# AeroModule_2021-02-14.net
KiCad netlist of a schematic drawn in EasyEDA
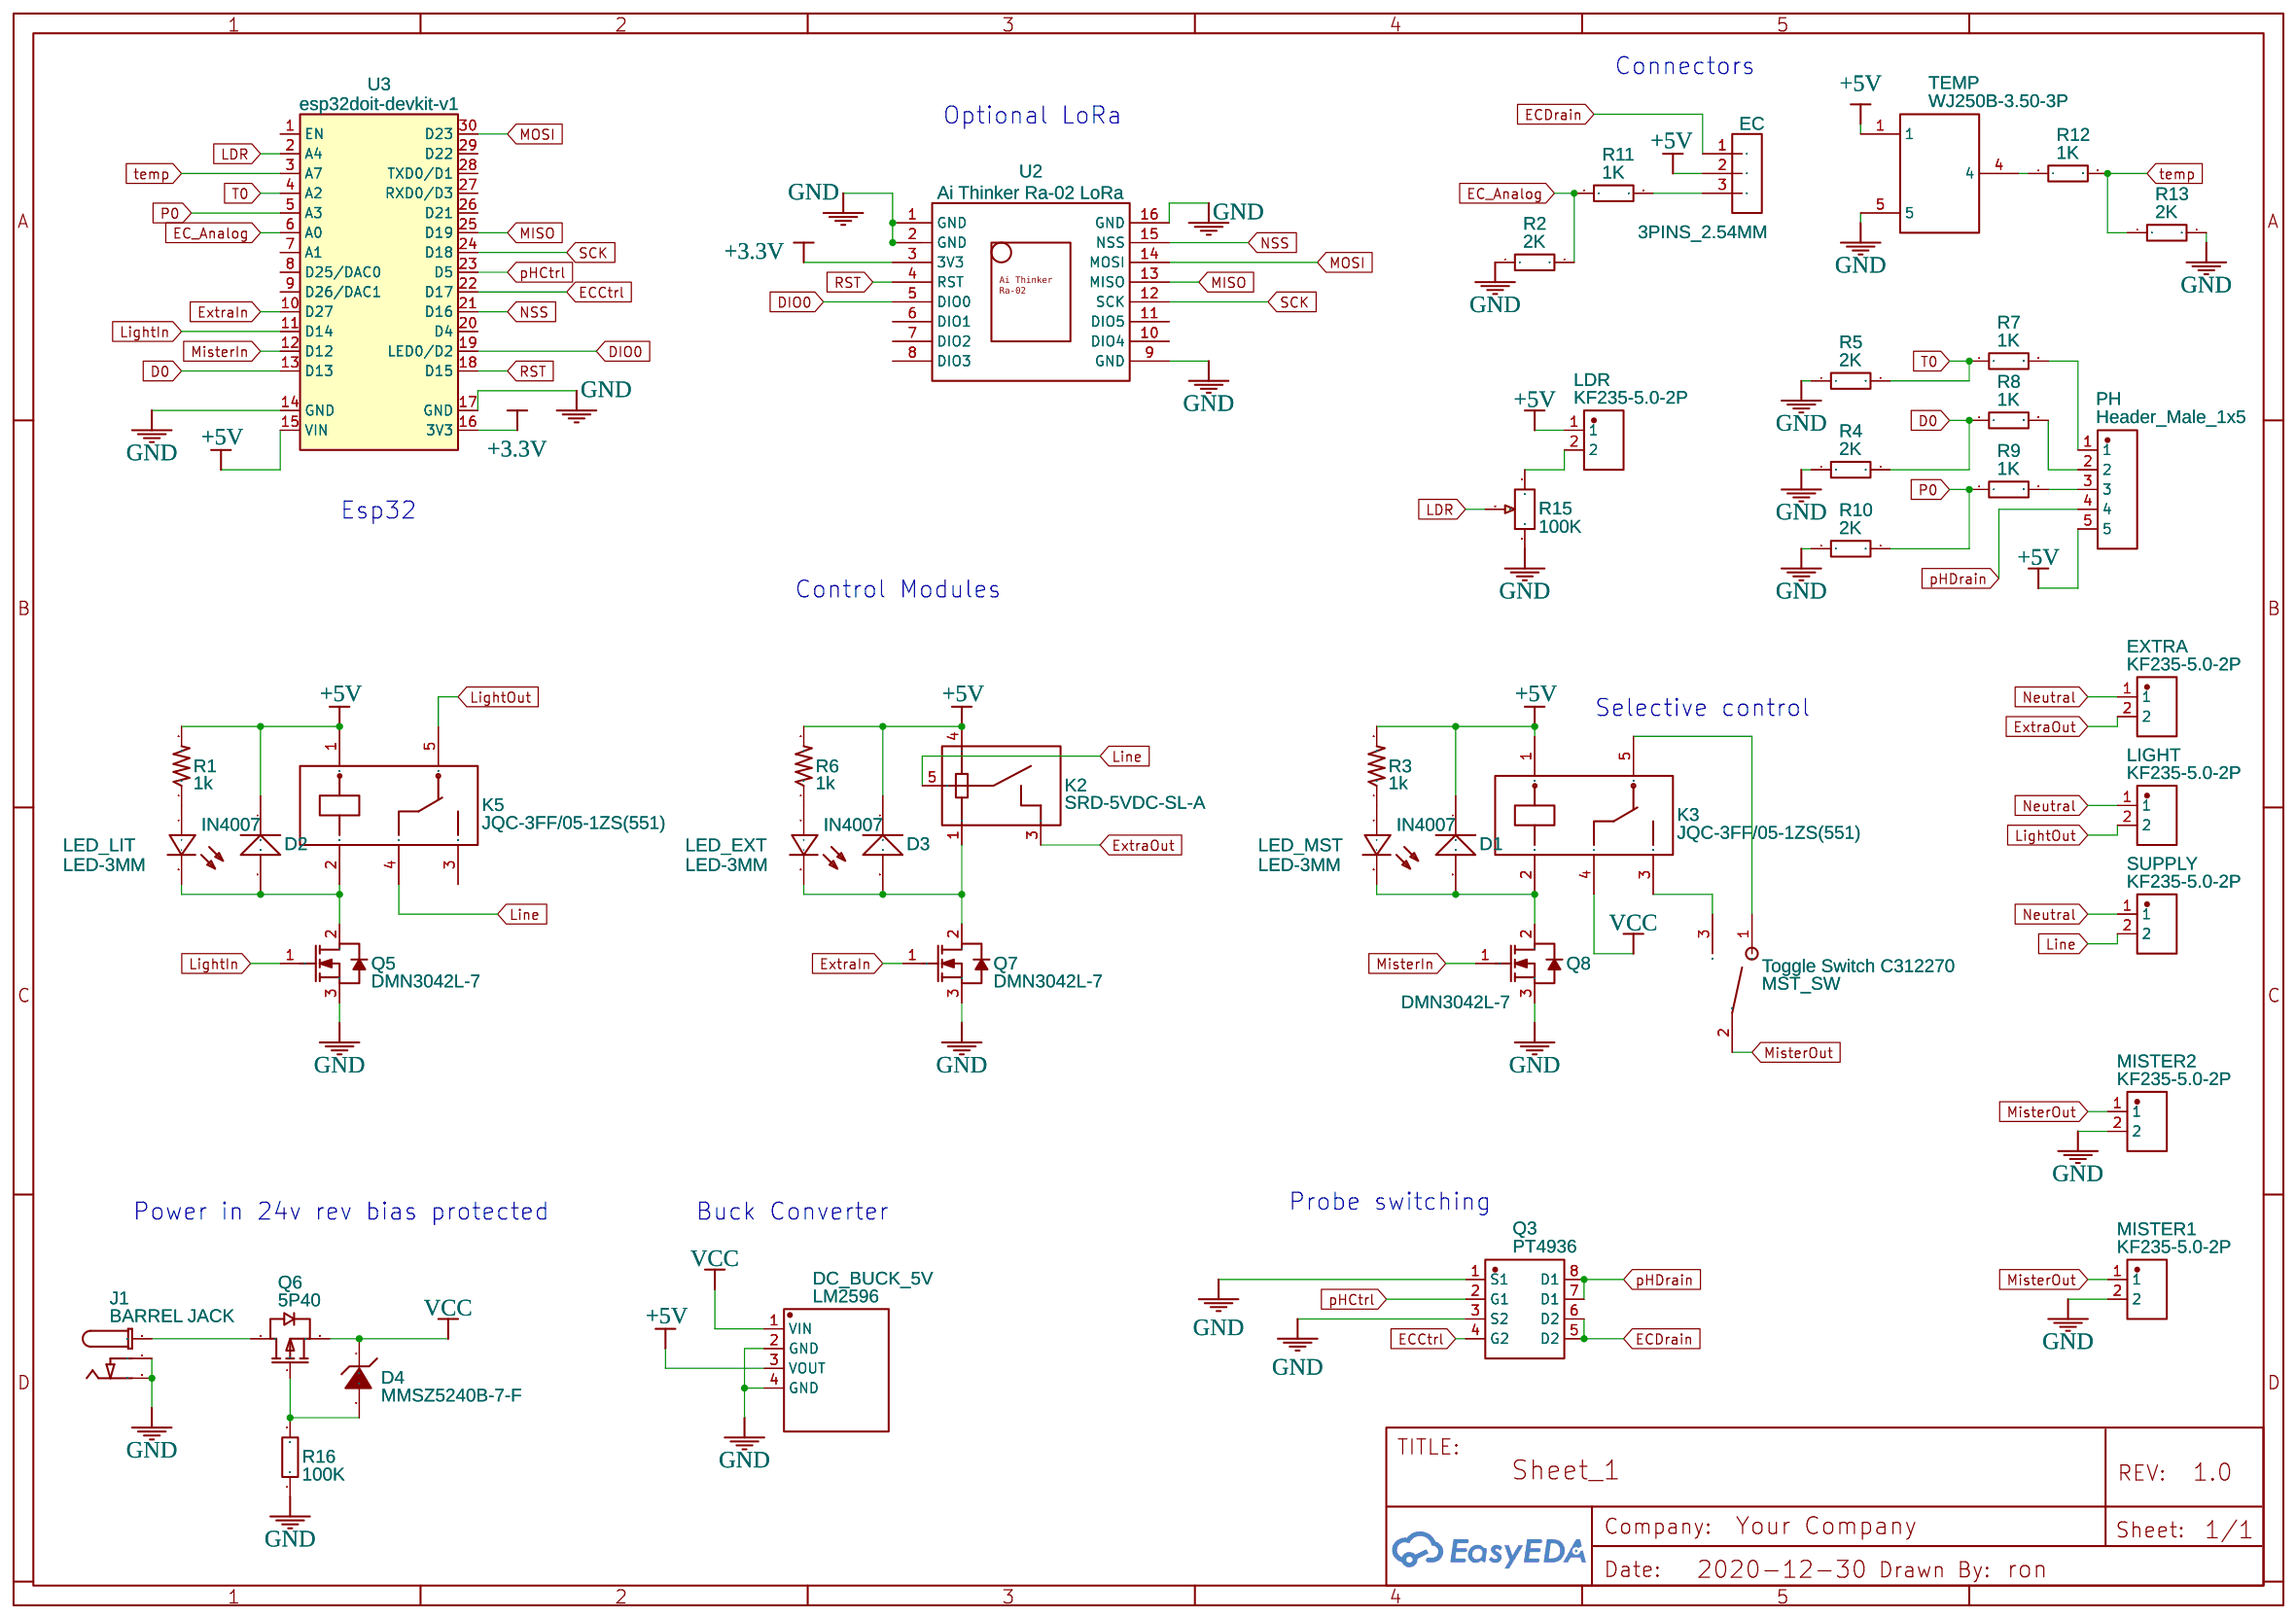
[diagram p0: Sheet_1]
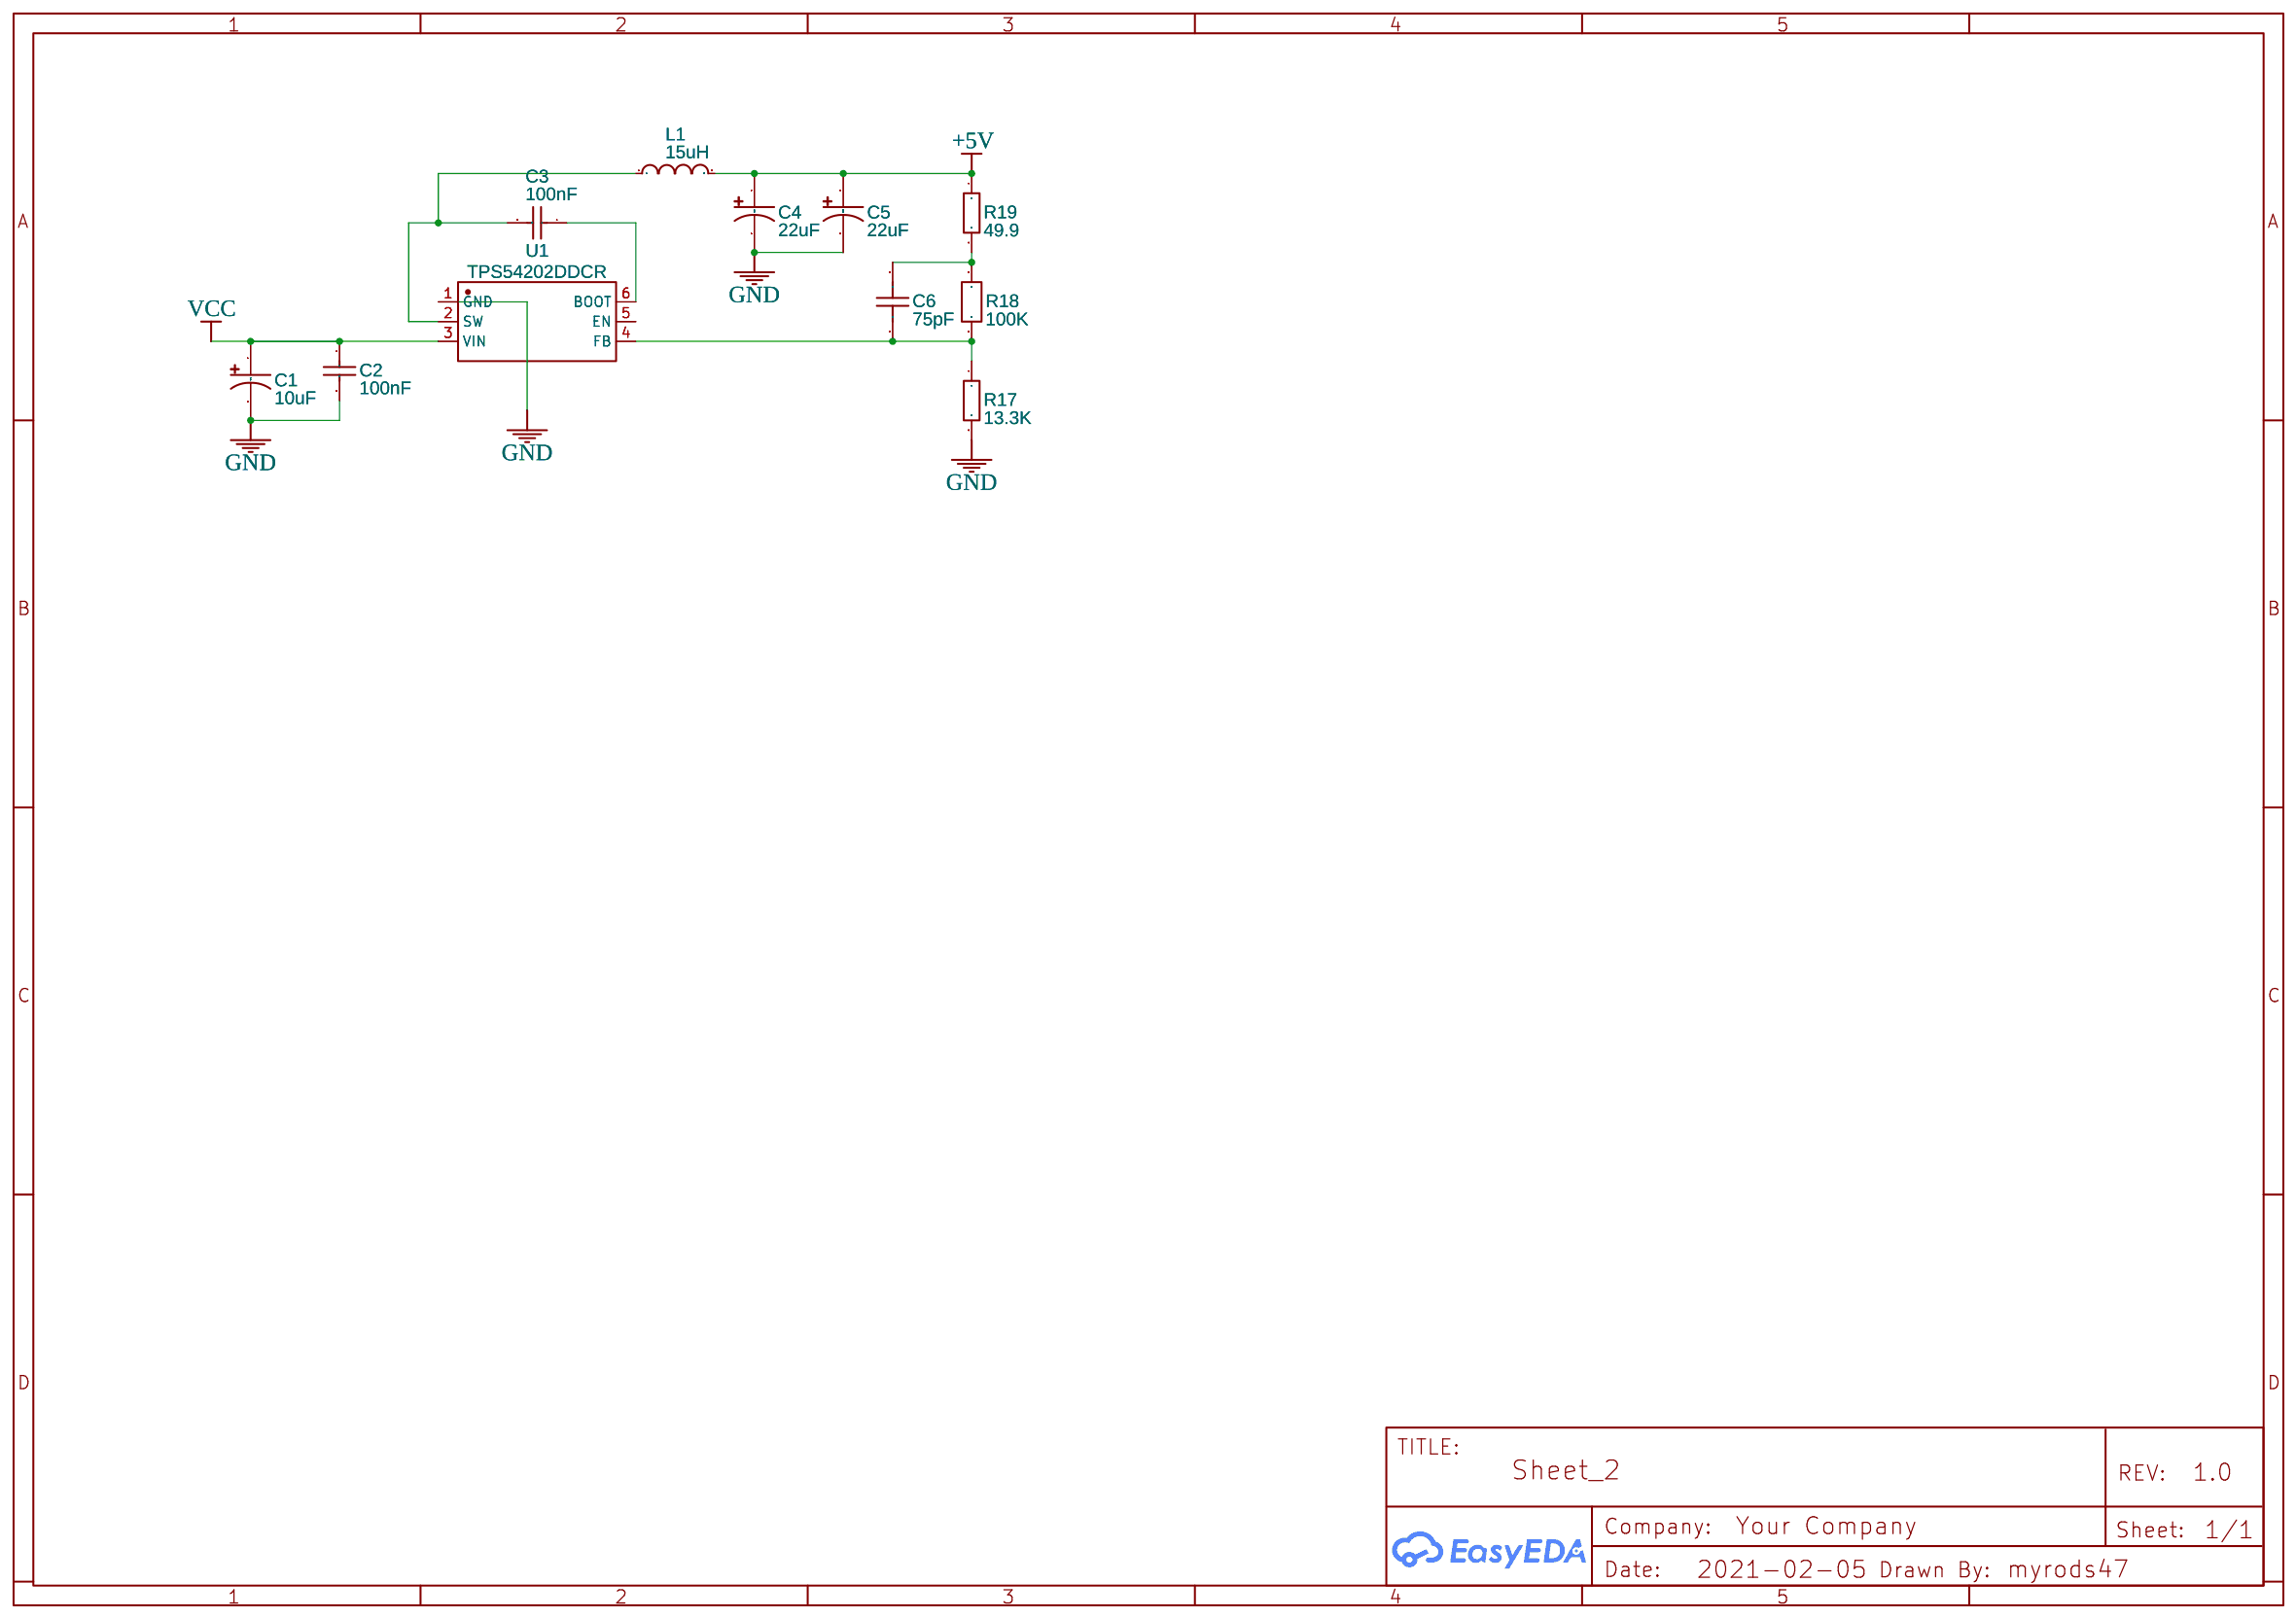
[diagram p1: Power]

(export (version "E")
  (design (tool "Eeschema 10.0.6"))
  (components
    (comp (ref "D1")
      (value "IN4007")
      (fields (field (name "BOM_Manufacturer Part") "IRFD9120PbF"))
      (libsource (lib "") (part "Unknown_730_-390"))
    )
    (comp (ref "D2")
      (value "IN4007")
      (fields (field (name "BOM_Manufacturer Part") "IRFD9120PbF"))
      (libsource (lib "") (part "Unknown_125_-390"))
    )
    (comp (ref "D3")
      (value "IN4007")
      (fields (field (name "BOM_Manufacturer Part") "IRFD9120PbF"))
      (libsource (lib "") (part "Unknown_440_-390"))
    )
    (comp (ref "D4")
      (value "MMSZ5240B-7-F")
      (fields (field (name "BOM_Supplier Part") "C151060"))
      (libsource (lib "") (part "MMSZ5240B-7-F"))
    )
    (comp (ref "DC_BUCK_5V") (value "LM2596") (libsource (lib "") (part "LM2596")))
    (comp (ref "EC")
      (value "3PINS_2.54MM")
      (fields (field (name "BOM_Supplier Part") "undefined"))
      (libsource (lib "") (part "3PINS_2.54MM"))
    )
    (comp (ref "EXTRA")
      (value "KF235-5.0-2P")
      (fields (field (name "BOM_Supplier Part") "C475172"))
      (libsource (lib "") (part "KF235-5.0-2P_3"))
    )
    (comp (ref "J1") (value "BARREL JACK") (libsource (lib "") (part "BARREL JACK")))
    (comp (ref "K2")
      (value "SRD-5VDC-SL-A")
      (fields (field (name "BOM_Supplier Part") "C140615"))
      (libsource (lib "") (part "Unknown_490_-415"))
    )
    (comp (ref "K3")
      (value "JQC-3FF/05-1ZS(551)")
      (fields (field (name "BOM_Supplier Part") "C9221"))
      (libsource (lib "") (part "JQC-3FF/05-1ZS(551)"))
    )
    (comp (ref "K5")
      (value "JQC-3FF/05-1ZS(551)")
      (fields (field (name "BOM_Supplier Part") "C9221"))
      (libsource (lib "") (part "JQC-3FF/05-1ZS(551)"))
    )
    (comp (ref "LDR")
      (value "KF235-5.0-2P")
      (fields (field (name "BOM_Supplier Part") "C475172"))
      (libsource (lib "") (part "KF235-5.0-2P"))
    )
    (comp (ref "LED_EXT")
      (value "LED-3MM")
      (fields
        (field (name "BOM_Manufacturer Part") "204-10SURD/S530-A3")
        (field (name "BOM_Supplier Part") "C99772")
      )
      (libsource (lib "") (part "Unknown_405_-385"))
    )
    (comp (ref "LED_LIT")
      (value "LED-3MM")
      (fields
        (field (name "BOM_Manufacturer Part") "204-10SURD/S530-A3")
        (field (name "BOM_Supplier Part") "C99772")
      )
      (libsource (lib "") (part "Unknown_90_-385"))
    )
    (comp (ref "LED_MST")
      (value "LED-3MM")
      (fields
        (field (name "BOM_Manufacturer Part") "204-10SURD/S530-A3")
        (field (name "BOM_Supplier Part") "C99772")
      )
      (libsource (lib "") (part "Unknown_695_-385"))
    )
    (comp (ref "LIGHT")
      (value "KF235-5.0-2P")
      (fields (field (name "BOM_Supplier Part") "C475172"))
      (libsource (lib "") (part "KF235-5.0-2P_4"))
    )
    (comp (ref "MISTER1")
      (value "KF235-5.0-2P")
      (fields (field (name "BOM_Supplier Part") "C475172"))
      (libsource (lib "") (part "KF235-5.0-2P_1"))
    )
    (comp (ref "MISTER2")
      (value "KF235-5.0-2P")
      (fields (field (name "BOM_Supplier Part") "C475172"))
      (libsource (lib "") (part "KF235-5.0-2P_1"))
    )
    (comp (ref "MST_SW")
      (value "Toggle Switch C312270")
      (fields
        (field (name "BOM_Manufacturer Part") "ST-1-102-A01-T000-RS")
        (field (name "BOM_Supplier Part") "C312270")
      )
      (libsource (lib "") (part "Toggle Switch C312270"))
    )
    (comp (ref "PH") (value "Header_Male_1x5") (libsource (lib "") (part "Header_Male_1x5")))
    (comp (ref "Q3")
      (value "PT4936")
      (fields (field (name "BOM_Supplier Part") "C479040"))
      (libsource (lib "") (part "PT4936"))
    )
    (comp (ref "Q5")
      (value "DMN3042L-7")
      (fields (field (name "BOM_Supplier Part") "C102621"))
      (libsource (lib "") (part "DMN3042L-7"))
    )
    (comp (ref "Q6")
      (value "5P40")
      (fields (field (name "BOM_Supplier Part") "C239051"))
      (libsource (lib "") (part "5P40"))
    )
    (comp (ref "Q7")
      (value "DMN3042L-7")
      (fields (field (name "BOM_Supplier Part") "C102621"))
      (libsource (lib "") (part "DMN3042L-7"))
    )
    (comp (ref "Q8")
      (value "DMN3042L-7")
      (fields (field (name "BOM_Supplier Part") "C102621"))
      (libsource (lib "") (part "DMN3042L-7"))
    )
    (comp (ref "R1")
      (value "1k")
      (fields (field (name "BOM_Manufacturer Part") "?"))
      (libsource (lib "") (part "Unknown_85_-425"))
    )
    (comp (ref "R2")
      (value "2K")
      (fields
        (field (name "BOM_Manufacturer Part") "ARG06FTC2001")
        (field (name "BOM_Supplier Part") "C294132")
      )
      (libsource (lib "") (part "ARG06FTC2001"))
    )
    (comp (ref "R3")
      (value "1k")
      (fields (field (name "BOM_Manufacturer Part") "?"))
      (libsource (lib "") (part "Unknown_690_-425"))
    )
    (comp (ref "R4")
      (value "2K")
      (fields
        (field (name "BOM_Manufacturer Part") "ARG06FTC2001")
        (field (name "BOM_Supplier Part") "C294132")
      )
      (libsource (lib "") (part "ARG06FTC2001"))
    )
    (comp (ref "R5")
      (value "2K")
      (fields
        (field (name "BOM_Manufacturer Part") "ARG06FTC2001")
        (field (name "BOM_Supplier Part") "C294132")
      )
      (libsource (lib "") (part "ARG06FTC2001"))
    )
    (comp (ref "R6")
      (value "1k")
      (fields (field (name "BOM_Manufacturer Part") "?"))
      (libsource (lib "") (part "Unknown_400_-425"))
    )
    (comp (ref "R7")
      (value "1K")
      (fields
        (field (name "BOM_Manufacturer Part") "ARG06FTC1001")
        (field (name "BOM_Supplier Part") "C294117")
      )
      (libsource (lib "") (part "ARG06FTC1001"))
    )
    (comp (ref "R8")
      (value "1K")
      (fields
        (field (name "BOM_Manufacturer Part") "ARG06FTC1001")
        (field (name "BOM_Supplier Part") "C294117")
      )
      (libsource (lib "") (part "ARG06FTC1001"))
    )
    (comp (ref "R9")
      (value "1K")
      (fields
        (field (name "BOM_Manufacturer Part") "ARG06FTC1001")
        (field (name "BOM_Supplier Part") "C294117")
      )
      (libsource (lib "") (part "ARG06FTC1001"))
    )
    (comp (ref "R10")
      (value "2K")
      (fields
        (field (name "BOM_Manufacturer Part") "ARG06FTC2001")
        (field (name "BOM_Supplier Part") "C294132")
      )
      (libsource (lib "") (part "ARG06FTC2001"))
    )
    (comp (ref "R11")
      (value "1K")
      (fields
        (field (name "BOM_Manufacturer Part") "ARG06FTC1001")
        (field (name "BOM_Supplier Part") "C294117")
      )
      (libsource (lib "") (part "ARG06FTC1001"))
    )
    (comp (ref "R12")
      (value "1K")
      (fields
        (field (name "BOM_Manufacturer Part") "ARG06FTC1001")
        (field (name "BOM_Supplier Part") "C294117")
      )
      (libsource (lib "") (part "ARG06FTC1001"))
    )
    (comp (ref "R13")
      (value "2K")
      (fields
        (field (name "BOM_Manufacturer Part") "ARG06FTC2001")
        (field (name "BOM_Supplier Part") "C294132")
      )
      (libsource (lib "") (part "ARG06FTC2001"))
    )
    (comp (ref "R15")
      (value "100K")
      (fields
        (field (name "BOM_Manufacturer Part") "3296W-1-104")
        (field (name "BOM_Supplier Part") "C118963")
      )
      (libsource (lib "") (part "3296W-1-104"))
    )
    (comp (ref "R16")
      (value "100K")
      (fields
        (field (name "BOM_Manufacturer Part") "AR06FTCV1003")
        (field (name "BOM_Supplier Part") "C412413")
      )
      (libsource (lib "") (part "AR06FTCV1003"))
    )
    (comp (ref "SUPPLY")
      (value "KF235-5.0-2P")
      (fields (field (name "BOM_Supplier Part") "C475172"))
      (libsource (lib "") (part "KF235-5.0-2P_2"))
    )
    (comp (ref "TEMP")
      (value "WJ250B-3.50-3P")
      (fields (field (name "BOM_Supplier Part") "C8420"))
      (libsource (lib "") (part "WJ250B-3.50-3P"))
    )
    (comp (ref "U2") (value "Ai Thinker Ra-02 LoRa") (libsource (lib "") (part "Ai Thinker Ra-02 LoRa")))
    (comp (ref "U3")
      (value "esp32doit-devkit-v1")
      (libsource (lib "") (part "esp32_devkit_v1_doit_ESP32_DevKit_V1_DOIT"))
    )
    (comp (ref "C1")
      (value "10uF")
      (fields
        (field (name "BOM_Manufacturer Part") "EEEHB1V100AR")
        (field (name "BOM_Supplier Part") "C336504")
      )
      (libsource (lib "") (part "EEEHB1V100AR"))
    )
    (comp (ref "C2")
      (value "100nF")
      (fields
        (field (name "BOM_Manufacturer Part") "CL31B104KBCNNNC")
        (field (name "BOM_Supplier Part") "C24497")
      )
      (libsource (lib "") (part "CL31B104KBCNNNC_1"))
    )
    (comp (ref "C3")
      (value "100nF")
      (fields
        (field (name "BOM_Manufacturer Part") "CL31B104KBCNNNC")
        (field (name "BOM_Supplier Part") "C24497")
      )
      (libsource (lib "") (part "CL31B104KBCNNNC"))
    )
    (comp (ref "C4")
      (value "22uF")
      (fields
        (field (name "BOM_Manufacturer Part") "CK1V220M-CRE54")
        (field (name "BOM_Supplier Part") "C190079")
      )
      (libsource (lib "") (part "CK1V220M-CRE54"))
    )
    (comp (ref "C5")
      (value "22uF")
      (fields
        (field (name "BOM_Manufacturer Part") "CK1V220M-CRE54")
        (field (name "BOM_Supplier Part") "C190079")
      )
      (libsource (lib "") (part "CK1V220M-CRE54"))
    )
    (comp (ref "C6")
      (value "75pF")
      (fields
        (field (name "BOM_Manufacturer Part") "CC0805JRNPO9BN750")
        (field (name "BOM_Supplier Part") "C113832")
      )
      (libsource (lib "") (part "CC0805JRNPO9BN750"))
    )
    (comp (ref "L1")
      (value "15uH")
      (fields
        (field (name "BOM_Manufacturer Part") "CR5040-150M")
        (field (name "BOM_Supplier Part") "C520353")
      )
      (libsource (lib "") (part "CR5040-150M"))
    )
    (comp (ref "R17")
      (value "13.3K")
      (fields
        (field (name "BOM_Manufacturer Part") "TR1206B13K3P0550")
        (field (name "BOM_Supplier Part") "C153316")
      )
      (libsource (lib "") (part "TR1206B13K3P0550"))
    )
    (comp (ref "R18")
      (value "100K")
      (fields
        (field (name "BOM_Manufacturer Part") "TC0650F1003T5E")
        (field (name "BOM_Supplier Part") "C425571")
      )
      (libsource (lib "") (part "TC0650F1003T5E"))
    )
    (comp (ref "R19")
      (value "49.9")
      (fields
        (field (name "BOM_Manufacturer Part") "TC0525F499JT5E")
        (field (name "BOM_Supplier Part") "C78599")
      )
      (libsource (lib "") (part "TC0525F499JT5E"))
    )
    (comp (ref "U1")
      (value "TPS54202DDCR")
      (fields (field (name "BOM_Supplier Part") "C191884"))
      (libsource (lib "") (part "TPS54202DDCR"))
    )
  )
  (nets
    (net (code "1") (name "+3.3V") (class "Default")
      (node (ref "U2") (pin "3") (pinfunction "3V3_3") (pintype "unspecified"))
      (node (ref "U3") (pin "16") (pinfunction "3V3_16") (pintype "bidirectional"))
    )
    (net (code "2") (name "+5V") (class "Default")
      (node (ref "C4") (pin "1") (pinfunction "1_1") (pintype "unspecified"))
      (node (ref "C5") (pin "1") (pinfunction "1_1") (pintype "unspecified"))
      (node (ref "D1") (pin "1") (pinfunction "1_1") (pintype "unspecified"))
      (node (ref "D2") (pin "1") (pinfunction "1_1") (pintype "unspecified"))
      (node (ref "D3") (pin "1") (pinfunction "1_1") (pintype "unspecified"))
      (node (ref "DC_BUCK_5V") (pin "3") (pinfunction "VOUT_3") (pintype "unspecified"))
      (node (ref "EC") (pin "2") (pinfunction "2_2") (pintype "unspecified"))
      (node (ref "K2") (pin "4") (pinfunction "4_4") (pintype "unspecified"))
      (node (ref "K3") (pin "1") (pinfunction "1_1") (pintype "input"))
      (node (ref "K5") (pin "1") (pinfunction "1_1") (pintype "input"))
      (node (ref "L1") (pin "2") (pinfunction "2_2") (pintype "unspecified"))
      (node (ref "LDR") (pin "1") (pinfunction "1_1") (pintype "unspecified"))
      (node (ref "PH") (pin "5") (pinfunction "5_5") (pintype "unspecified"))
      (node (ref "R1") (pin "2") (pinfunction "2_2") (pintype "unspecified"))
      (node (ref "R19") (pin "1") (pinfunction "1_1") (pintype "input"))
      (node (ref "R3") (pin "2") (pinfunction "2_2") (pintype "unspecified"))
      (node (ref "R6") (pin "2") (pinfunction "2_2") (pintype "unspecified"))
      (node (ref "TEMP") (pin "1") (pinfunction "1_1") (pintype "unspecified"))
      (node (ref "U3") (pin "15") (pinfunction "VIN_15") (pintype "bidirectional"))
    )
    (net (code "3") (name "D0") (class "Default")
      (node (ref "R4") (pin "2") (pinfunction "2_2") (pintype "unspecified"))
      (node (ref "R8") (pin "1") (pinfunction "1_1") (pintype "unspecified"))
      (node (ref "U3") (pin "13") (pinfunction "D13_13") (pintype "bidirectional"))
    )
    (net (code "4") (name "DIO0") (class "Default")
      (node (ref "U2") (pin "5") (pinfunction "DIO0_5") (pintype "unspecified"))
      (node (ref "U3") (pin "19") (pinfunction "LED0/D2_19") (pintype "bidirectional"))
    )
    (net (code "5") (name "ECCtrl") (class "Default")
      (node (ref "Q3") (pin "4") (pinfunction "G2_4") (pintype "unspecified"))
      (node (ref "U3") (pin "22") (pinfunction "D17_22") (pintype "bidirectional"))
    )
    (net (code "6") (name "ECDrain") (class "Default")
      (node (ref "EC") (pin "1") (pinfunction "1_1") (pintype "unspecified"))
      (node (ref "Q3") (pin "5") (pinfunction "D2_5") (pintype "unspecified"))
      (node (ref "Q3") (pin "6") (pinfunction "D2_6") (pintype "unspecified"))
    )
    (net (code "7") (name "EC_Analog") (class "Default")
      (node (ref "R11") (pin "1") (pinfunction "1_1") (pintype "unspecified"))
      (node (ref "R2") (pin "2") (pinfunction "2_2") (pintype "unspecified"))
      (node (ref "U3") (pin "6") (pinfunction "A0_6") (pintype "bidirectional"))
    )
    (net (code "8") (name "ExtraIn") (class "Default")
      (node (ref "Q7") (pin "1") (pinfunction "G_1") (pintype "unspecified"))
      (node (ref "U3") (pin "10") (pinfunction "D27_10") (pintype "bidirectional"))
    )
    (net (code "9") (name "ExtraOut") (class "Default")
      (node (ref "EXTRA") (pin "2") (pinfunction "2_2") (pintype "unspecified"))
      (node (ref "K2") (pin "3") (pinfunction "3_3") (pintype "unspecified"))
    )
    (net (code "10") (name "GND") (class "Default")
      (node (ref "C1") (pin "2") (pinfunction "2_2") (pintype "unspecified"))
      (node (ref "C2") (pin "2") (pinfunction "2_2") (pintype "input"))
      (node (ref "C4") (pin "2") (pinfunction "2_2") (pintype "unspecified"))
      (node (ref "C5") (pin "2") (pinfunction "2_2") (pintype "unspecified"))
      (node (ref "DC_BUCK_5V") (pin "2") (pinfunction "GND_2") (pintype "unspecified"))
      (node (ref "DC_BUCK_5V") (pin "4") (pinfunction "GND_4") (pintype "unspecified"))
      (node (ref "J1") (pin "P2") (pinfunction "P3_P2") (pintype "unspecified"))
      (node (ref "J1") (pin "P3") (pinfunction "P2_P3") (pintype "unspecified"))
      (node (ref "MISTER1") (pin "2") (pinfunction "2_2") (pintype "unspecified"))
      (node (ref "MISTER2") (pin "2") (pinfunction "2_2") (pintype "unspecified"))
      (node (ref "Q3") (pin "1") (pinfunction "S1_1") (pintype "unspecified"))
      (node (ref "Q3") (pin "3") (pinfunction "S2_3") (pintype "unspecified"))
      (node (ref "Q5") (pin "3") (pinfunction "S_3") (pintype "unspecified"))
      (node (ref "Q7") (pin "3") (pinfunction "S_3") (pintype "unspecified"))
      (node (ref "Q8") (pin "3") (pinfunction "S_3") (pintype "unspecified"))
      (node (ref "R10") (pin "1") (pinfunction "1_1") (pintype "unspecified"))
      (node (ref "R13") (pin "2") (pinfunction "2_2") (pintype "unspecified"))
      (node (ref "R15") (pin "1") (pinfunction "1_1") (pintype "input"))
      (node (ref "R16") (pin "1") (pinfunction "1_1") (pintype "unspecified"))
      (node (ref "R17") (pin "2") (pinfunction "2_2") (pintype "unspecified"))
      (node (ref "R2") (pin "1") (pinfunction "1_1") (pintype "unspecified"))
      (node (ref "R4") (pin "1") (pinfunction "1_1") (pintype "unspecified"))
      (node (ref "R5") (pin "1") (pinfunction "1_1") (pintype "unspecified"))
      (node (ref "TEMP") (pin "5") (pinfunction "5_5") (pintype "unspecified"))
      (node (ref "U1") (pin "1") (pinfunction "GND_1") (pintype "unspecified"))
      (node (ref "U2") (pin "1") (pinfunction "GND_1") (pintype "unspecified"))
      (node (ref "U2") (pin "16") (pinfunction "GND_16") (pintype "unspecified"))
      (node (ref "U2") (pin "2") (pinfunction "GND_2") (pintype "unspecified"))
      (node (ref "U2") (pin "9") (pinfunction "GND_9") (pintype "unspecified"))
      (node (ref "U3") (pin "14") (pinfunction "GND_14") (pintype "bidirectional"))
      (node (ref "U3") (pin "17") (pinfunction "GND_17") (pintype "bidirectional"))
    )
    (net (code "11") (name "LDR") (class "Default")
      (node (ref "R15") (pin "2") (pinfunction "2_2") (pintype "input"))
      (node (ref "U3") (pin "2") (pinfunction "A4_2") (pintype "bidirectional"))
    )
    (net (code "12") (name "LightIn") (class "Default")
      (node (ref "Q5") (pin "1") (pinfunction "G_1") (pintype "unspecified"))
      (node (ref "U3") (pin "11") (pinfunction "D14_11") (pintype "bidirectional"))
    )
    (net (code "13") (name "LightOut") (class "Default")
      (node (ref "K5") (pin "5") (pinfunction "5_5") (pintype "input"))
      (node (ref "LIGHT") (pin "2") (pinfunction "2_2") (pintype "unspecified"))
    )
    (net (code "14") (name "Line") (class "Default")
      (node (ref "K2") (pin "5") (pinfunction "5_5") (pintype "unspecified"))
      (node (ref "K5") (pin "4") (pinfunction "4_4") (pintype "input"))
      (node (ref "SUPPLY") (pin "2") (pinfunction "2_2") (pintype "unspecified"))
    )
    (net (code "15") (name "MISO") (class "Default")
      (node (ref "U2") (pin "13") (pinfunction "MISO_13") (pintype "unspecified"))
      (node (ref "U3") (pin "25") (pinfunction "D19_25") (pintype "bidirectional"))
    )
    (net (code "16") (name "MOSI") (class "Default")
      (node (ref "U2") (pin "14") (pinfunction "MOSI_14") (pintype "unspecified"))
      (node (ref "U3") (pin "30") (pinfunction "D23_30") (pintype "bidirectional"))
    )
    (net (code "17") (name "MisterIn") (class "Default")
      (node (ref "Q8") (pin "1") (pinfunction "G_1") (pintype "unspecified"))
      (node (ref "U3") (pin "12") (pinfunction "D12_12") (pintype "bidirectional"))
    )
    (net (code "18") (name "MisterOut") (class "Default")
      (node (ref "MISTER1") (pin "1") (pinfunction "1_1") (pintype "unspecified"))
      (node (ref "MISTER2") (pin "1") (pinfunction "1_1") (pintype "unspecified"))
      (node (ref "MST_SW") (pin "2") (pinfunction "2_2") (pintype "input"))
    )
    (net (code "19") (name "NSS") (class "Default")
      (node (ref "U2") (pin "15") (pinfunction "NSS_15") (pintype "unspecified"))
      (node (ref "U3") (pin "21") (pinfunction "D16_21") (pintype "bidirectional"))
    )
    (net (code "20") (name "Net-(C6-Pad2)") (class "Default")
      (node (ref "C6") (pin "2") (pinfunction "2_2") (pintype "unspecified"))
      (node (ref "R18") (pin "1") (pinfunction "1_1") (pintype "unspecified"))
      (node (ref "R19") (pin "2") (pinfunction "2_2") (pintype "input"))
    )
    (net (code "21") (name "Net-(D4-A)") (class "Default")
      (node (ref "D4") (pin "2") (pinfunction "A_2") (pintype "unspecified"))
      (node (ref "Q6") (pin "1") (pinfunction "G_1") (pintype "unspecified"))
      (node (ref "R16") (pin "2") (pinfunction "2_2") (pintype "unspecified"))
    )
    (net (code "22") (name "Net-(EC-Pad3)") (class "Default")
      (node (ref "EC") (pin "3") (pinfunction "3_3") (pintype "unspecified"))
      (node (ref "R11") (pin "2") (pinfunction "2_2") (pintype "unspecified"))
    )
    (net (code "23") (name "Net-(K3-Pad3)") (class "Default")
      (node (ref "K3") (pin "3") (pinfunction "3_3") (pintype "input"))
      (node (ref "MST_SW") (pin "3") (pinfunction "3_3") (pintype "input"))
    )
    (net (code "24") (name "Net-(K3-Pad5)") (class "Default")
      (node (ref "K3") (pin "5") (pinfunction "5_5") (pintype "input"))
      (node (ref "MST_SW") (pin "1") (pinfunction "1_1") (pintype "input"))
    )
    (net (code "25") (name "Net-(LDR-Pad2)") (class "Default")
      (node (ref "LDR") (pin "2") (pinfunction "2_2") (pintype "unspecified"))
      (node (ref "R15") (pin "3") (pinfunction "3_3") (pintype "input"))
    )
    (net (code "26") (name "Net-(LED_EXT-+)") (class "Default")
      (node (ref "LED_EXT") (pin "1") (pinfunction "+_1") (pintype "unspecified"))
      (node (ref "R6") (pin "1") (pinfunction "1_1") (pintype "unspecified"))
    )
    (net (code "27") (name "Net-(LED_EXT--)") (class "Default")
      (node (ref "D3") (pin "2") (pinfunction "2_2") (pintype "unspecified"))
      (node (ref "K2") (pin "1") (pinfunction "1_1") (pintype "unspecified"))
      (node (ref "LED_EXT") (pin "2") (pinfunction "-_2") (pintype "unspecified"))
      (node (ref "Q7") (pin "2") (pinfunction "D_2") (pintype "unspecified"))
    )
    (net (code "28") (name "Net-(LED_LIT-+)") (class "Default")
      (node (ref "LED_LIT") (pin "1") (pinfunction "+_1") (pintype "unspecified"))
      (node (ref "R1") (pin "1") (pinfunction "1_1") (pintype "unspecified"))
    )
    (net (code "29") (name "Net-(LED_LIT--)") (class "Default")
      (node (ref "D2") (pin "2") (pinfunction "2_2") (pintype "unspecified"))
      (node (ref "K5") (pin "2") (pinfunction "2_2") (pintype "input"))
      (node (ref "LED_LIT") (pin "2") (pinfunction "-_2") (pintype "unspecified"))
      (node (ref "Q5") (pin "2") (pinfunction "D_2") (pintype "unspecified"))
    )
    (net (code "30") (name "Net-(LED_MST-+)") (class "Default")
      (node (ref "LED_MST") (pin "1") (pinfunction "+_1") (pintype "unspecified"))
      (node (ref "R3") (pin "1") (pinfunction "1_1") (pintype "unspecified"))
    )
    (net (code "31") (name "Net-(LED_MST--)") (class "Default")
      (node (ref "D1") (pin "2") (pinfunction "2_2") (pintype "unspecified"))
      (node (ref "K3") (pin "2") (pinfunction "2_2") (pintype "input"))
      (node (ref "LED_MST") (pin "2") (pinfunction "-_2") (pintype "unspecified"))
      (node (ref "Q8") (pin "2") (pinfunction "D_2") (pintype "unspecified"))
    )
    (net (code "32") (name "Net-(PH-Pad1)") (class "Default")
      (node (ref "PH") (pin "1") (pinfunction "1_1") (pintype "unspecified"))
      (node (ref "R7") (pin "2") (pinfunction "2_2") (pintype "unspecified"))
    )
    (net (code "33") (name "Net-(PH-Pad2)") (class "Default")
      (node (ref "PH") (pin "2") (pinfunction "2_2") (pintype "unspecified"))
      (node (ref "R8") (pin "2") (pinfunction "2_2") (pintype "unspecified"))
    )
    (net (code "34") (name "Net-(PH-Pad3)") (class "Default")
      (node (ref "PH") (pin "3") (pinfunction "3_3") (pintype "unspecified"))
      (node (ref "R9") (pin "2") (pinfunction "2_2") (pintype "unspecified"))
    )
    (net (code "35") (name "Net-(Q6-D)") (class "Default")
      (node (ref "J1") (pin "P1") (pinfunction "P1_P1") (pintype "unspecified"))
      (node (ref "Q6") (pin "3") (pinfunction "D_3") (pintype "unspecified"))
    )
    (net (code "36") (name "Net-(R12-Pad1)") (class "Default")
      (node (ref "R12") (pin "1") (pinfunction "1_1") (pintype "unspecified"))
      (node (ref "TEMP") (pin "4") (pinfunction "4_4") (pintype "unspecified"))
    )
    (net (code "37") (name "Net-(U1-BOOT)") (class "Default")
      (node (ref "C3") (pin "1") (pinfunction "1_1") (pintype "input"))
      (node (ref "U1") (pin "6") (pinfunction "BOOT_6") (pintype "unspecified"))
    )
    (net (code "38") (name "Net-(U1-FB)") (class "Default")
      (node (ref "C6") (pin "1") (pinfunction "1_1") (pintype "unspecified"))
      (node (ref "R17") (pin "1") (pinfunction "1_1") (pintype "unspecified"))
      (node (ref "R18") (pin "2") (pinfunction "2_2") (pintype "unspecified"))
      (node (ref "U1") (pin "4") (pinfunction "FB_4") (pintype "unspecified"))
    )
    (net (code "39") (name "Net-(U1-SW)") (class "Default")
      (node (ref "C3") (pin "2") (pinfunction "2_2") (pintype "input"))
      (node (ref "L1") (pin "1") (pinfunction "1_1") (pintype "unspecified"))
      (node (ref "U1") (pin "2") (pinfunction "SW_2") (pintype "unspecified"))
    )
    (net (code "40") (name "Neutral") (class "Default")
      (node (ref "EXTRA") (pin "1") (pinfunction "1_1") (pintype "unspecified"))
      (node (ref "LIGHT") (pin "1") (pinfunction "1_1") (pintype "unspecified"))
      (node (ref "SUPPLY") (pin "1") (pinfunction "1_1") (pintype "unspecified"))
    )
    (net (code "41") (name "P0") (class "Default")
      (node (ref "R10") (pin "2") (pinfunction "2_2") (pintype "unspecified"))
      (node (ref "R9") (pin "1") (pinfunction "1_1") (pintype "unspecified"))
      (node (ref "U3") (pin "5") (pinfunction "A3_5") (pintype "bidirectional"))
    )
    (net (code "42") (name "RST") (class "Default")
      (node (ref "U2") (pin "4") (pinfunction "RST_4") (pintype "unspecified"))
      (node (ref "U3") (pin "18") (pinfunction "D15_18") (pintype "bidirectional"))
    )
    (net (code "43") (name "SCK") (class "Default")
      (node (ref "U2") (pin "12") (pinfunction "SCK_12") (pintype "unspecified"))
      (node (ref "U3") (pin "24") (pinfunction "D18_24") (pintype "bidirectional"))
    )
    (net (code "44") (name "T0") (class "Default")
      (node (ref "R5") (pin "2") (pinfunction "2_2") (pintype "unspecified"))
      (node (ref "R7") (pin "1") (pinfunction "1_1") (pintype "unspecified"))
      (node (ref "U3") (pin "4") (pinfunction "A2_4") (pintype "bidirectional"))
    )
    (net (code "45") (name "VCC") (class "Default")
      (node (ref "C1") (pin "1") (pinfunction "1_1") (pintype "unspecified"))
      (node (ref "C2") (pin "1") (pinfunction "1_1") (pintype "input"))
      (node (ref "D4") (pin "1") (pinfunction "K_1") (pintype "unspecified"))
      (node (ref "DC_BUCK_5V") (pin "1") (pinfunction "VIN_1") (pintype "unspecified"))
      (node (ref "K3") (pin "4") (pinfunction "4_4") (pintype "input"))
      (node (ref "Q6") (pin "2") (pinfunction "S_2") (pintype "unspecified"))
      (node (ref "U1") (pin "3") (pinfunction "VIN_3") (pintype "unspecified"))
    )
    (net (code "46") (name "pHCtrl") (class "Default")
      (node (ref "Q3") (pin "2") (pinfunction "G1_2") (pintype "unspecified"))
      (node (ref "U3") (pin "23") (pinfunction "D5_23") (pintype "bidirectional"))
    )
    (net (code "47") (name "pHDrain") (class "Default")
      (node (ref "PH") (pin "4") (pinfunction "4_4") (pintype "unspecified"))
      (node (ref "Q3") (pin "7") (pinfunction "D1_7") (pintype "unspecified"))
      (node (ref "Q3") (pin "8") (pinfunction "D1_8") (pintype "unspecified"))
    )
    (net (code "48") (name "temp") (class "Default")
      (node (ref "R12") (pin "2") (pinfunction "2_2") (pintype "unspecified"))
      (node (ref "R13") (pin "1") (pinfunction "1_1") (pintype "unspecified"))
      (node (ref "U3") (pin "3") (pinfunction "A7_3") (pintype "bidirectional"))
    )
    (net (code "49") (name "unconnected-(K5-Pad3)") (class "Default")
      (node (ref "K5") (pin "3") (pinfunction "3_3") (pintype "input"))
    )
    (net (code "50") (name "unconnected-(U1-EN-Pad5)") (class "Default")
      (node (ref "U1") (pin "5") (pinfunction "EN_5") (pintype "unspecified"))
    )
    (net (code "51") (name "unconnected-(U2-DIO1-Pad6)") (class "Default")
      (node (ref "U2") (pin "6") (pinfunction "DIO1_6") (pintype "unspecified"))
    )
    (net (code "52") (name "unconnected-(U2-DIO2-Pad7)") (class "Default")
      (node (ref "U2") (pin "7") (pinfunction "DIO2_7") (pintype "unspecified"))
    )
    (net (code "53") (name "unconnected-(U2-DIO3-Pad8)") (class "Default")
      (node (ref "U2") (pin "8") (pinfunction "DIO3_8") (pintype "unspecified"))
    )
    (net (code "54") (name "unconnected-(U2-DIO4-Pad10)") (class "Default")
      (node (ref "U2") (pin "10") (pinfunction "DIO4_10") (pintype "unspecified"))
    )
    (net (code "55") (name "unconnected-(U2-DIO5-Pad11)") (class "Default")
      (node (ref "U2") (pin "11") (pinfunction "DIO5_11") (pintype "unspecified"))
    )
    (net (code "56") (name "unconnected-(U3-A1-Pad7)") (class "Default")
      (node (ref "U3") (pin "7") (pinfunction "A1_7") (pintype "bidirectional"))
    )
    (net (code "57") (name "unconnected-(U3-D4-Pad20)") (class "Default")
      (node (ref "U3") (pin "20") (pinfunction "D4_20") (pintype "bidirectional"))
    )
    (net (code "58") (name "unconnected-(U3-D21-Pad26)") (class "Default")
      (node (ref "U3") (pin "26") (pinfunction "D21_26") (pintype "bidirectional"))
    )
    (net (code "59") (name "unconnected-(U3-D22-Pad29)") (class "Default")
      (node (ref "U3") (pin "29") (pinfunction "D22_29") (pintype "bidirectional"))
    )
    (net (code "60") (name "unconnected-(U3-D25{slash}DAC0-Pad8)") (class "Default")
      (node (ref "U3") (pin "8") (pinfunction "D25/DAC0_8") (pintype "bidirectional"))
    )
    (net (code "61") (name "unconnected-(U3-D26{slash}DAC1-Pad9)") (class "Default")
      (node (ref "U3") (pin "9") (pinfunction "D26/DAC1_9") (pintype "bidirectional"))
    )
    (net (code "62") (name "unconnected-(U3-EN-Pad1)") (class "Default")
      (node (ref "U3") (pin "1") (pinfunction "EN_1") (pintype "input"))
    )
    (net (code "63") (name "unconnected-(U3-RXD0{slash}D3-Pad27)") (class "Default")
      (node (ref "U3") (pin "27") (pinfunction "RXD0/D3_27") (pintype "bidirectional"))
    )
    (net (code "64") (name "unconnected-(U3-TXD0{slash}D1-Pad28)") (class "Default")
      (node (ref "U3") (pin "28") (pinfunction "TXD0/D1_28") (pintype "bidirectional"))
    )
  )
)
